# main.net
KiCad netlist of a schematic drawn in Altium Designer
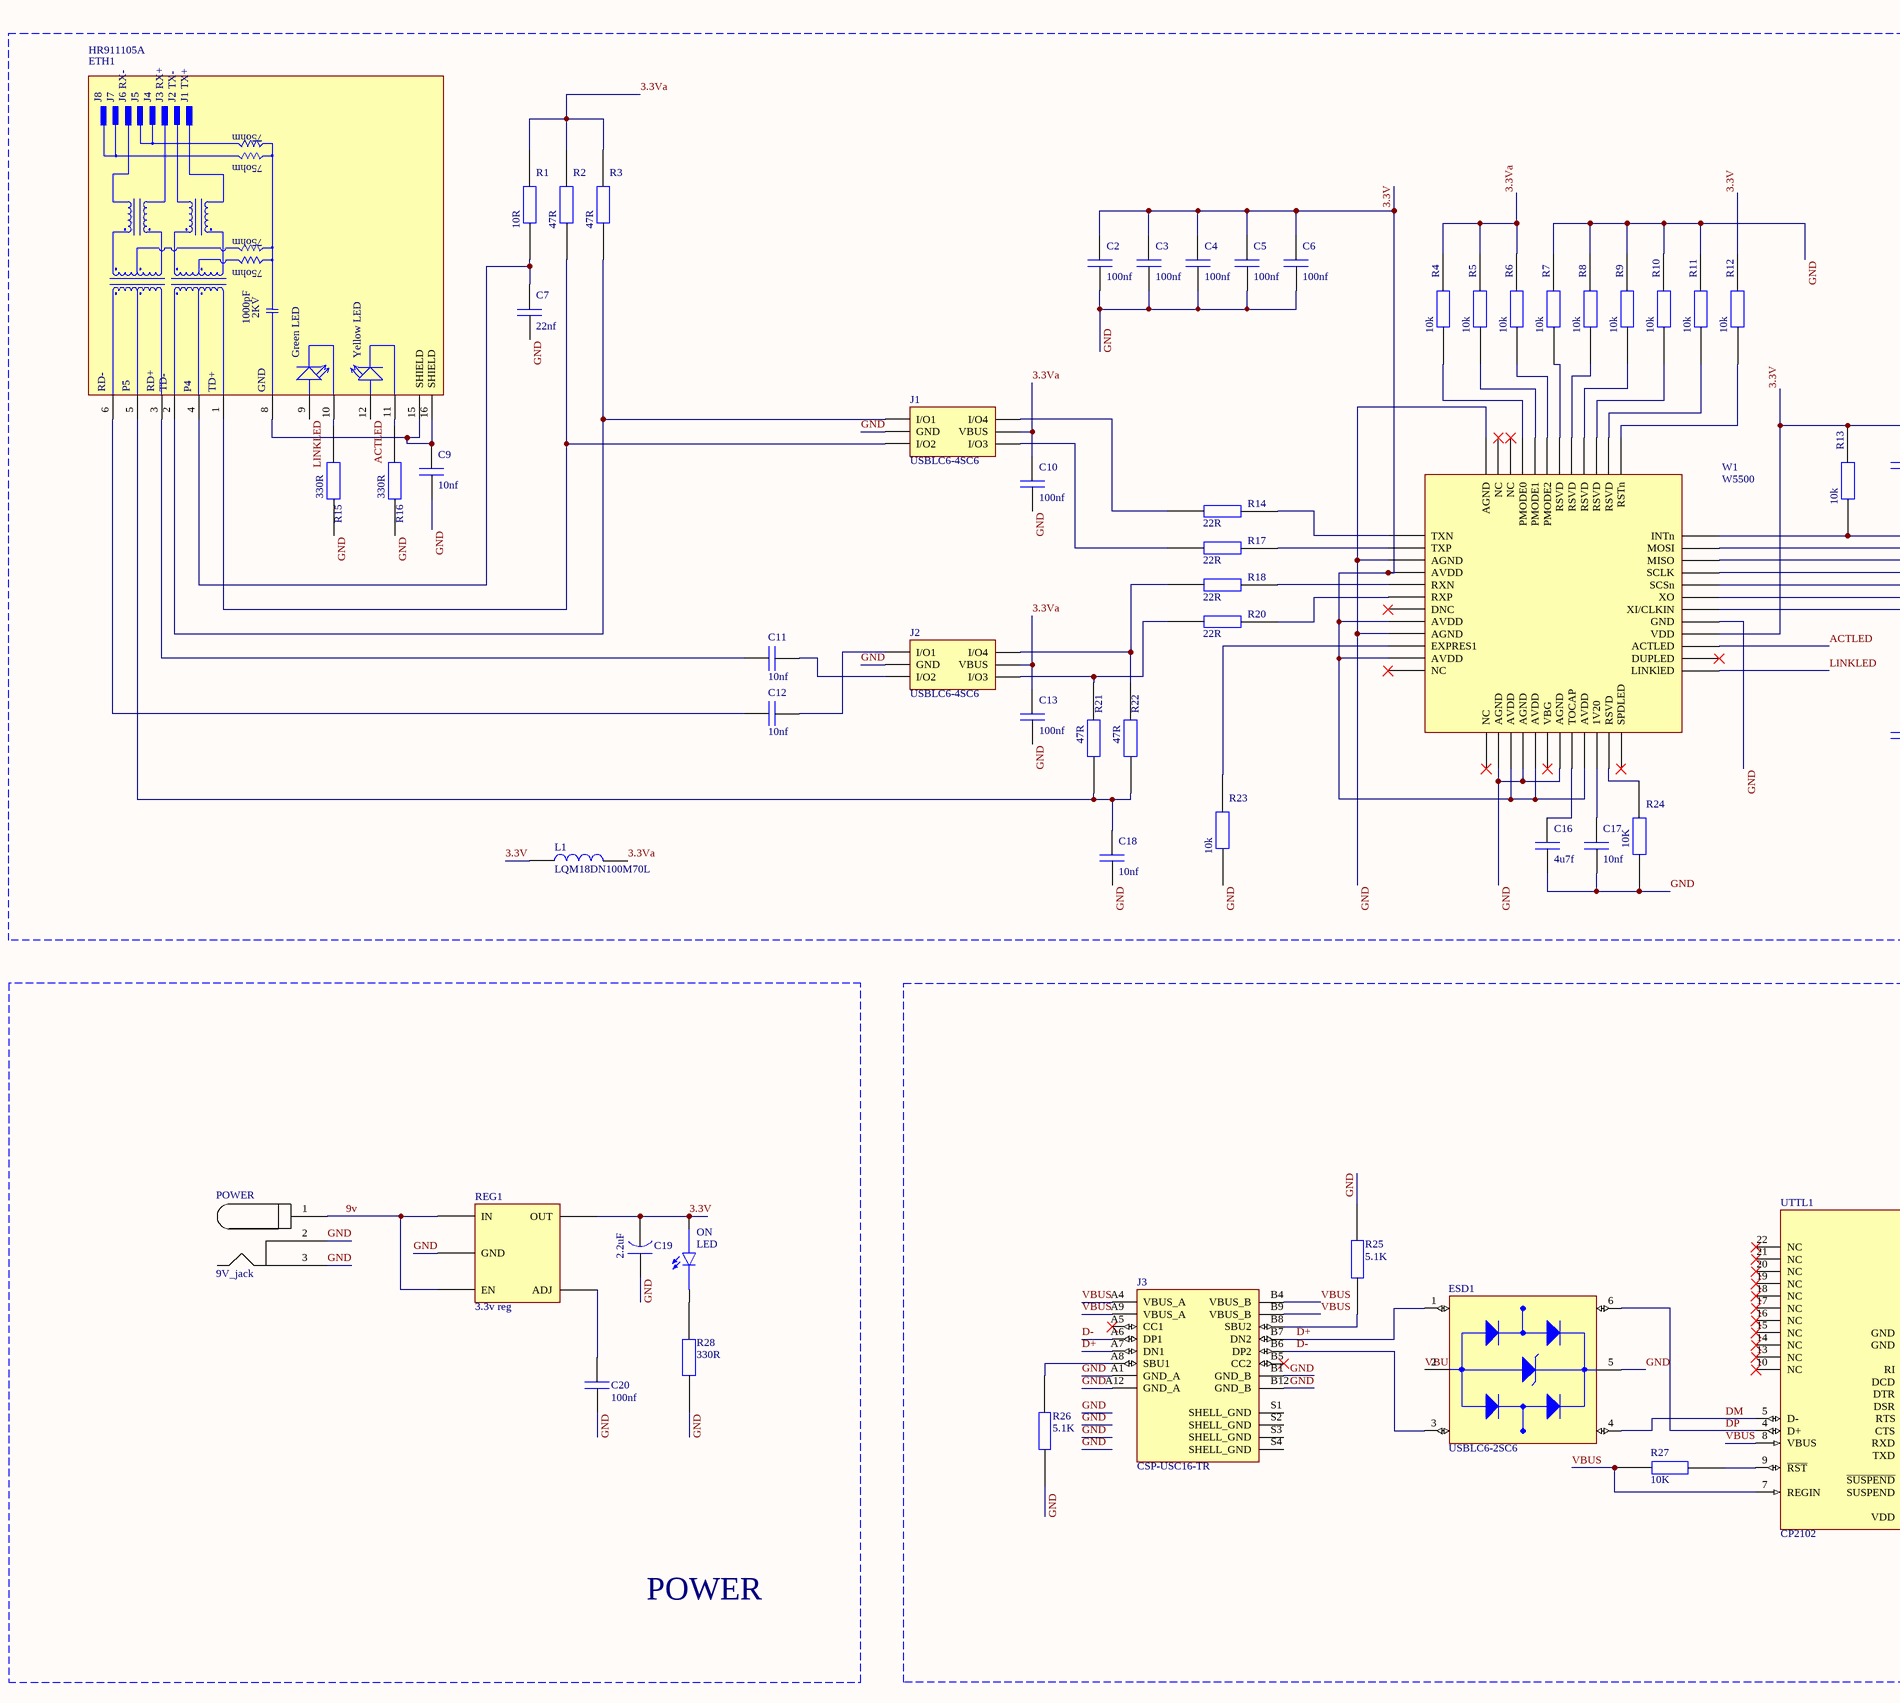
[diagram p0: main.SchDoc, left]
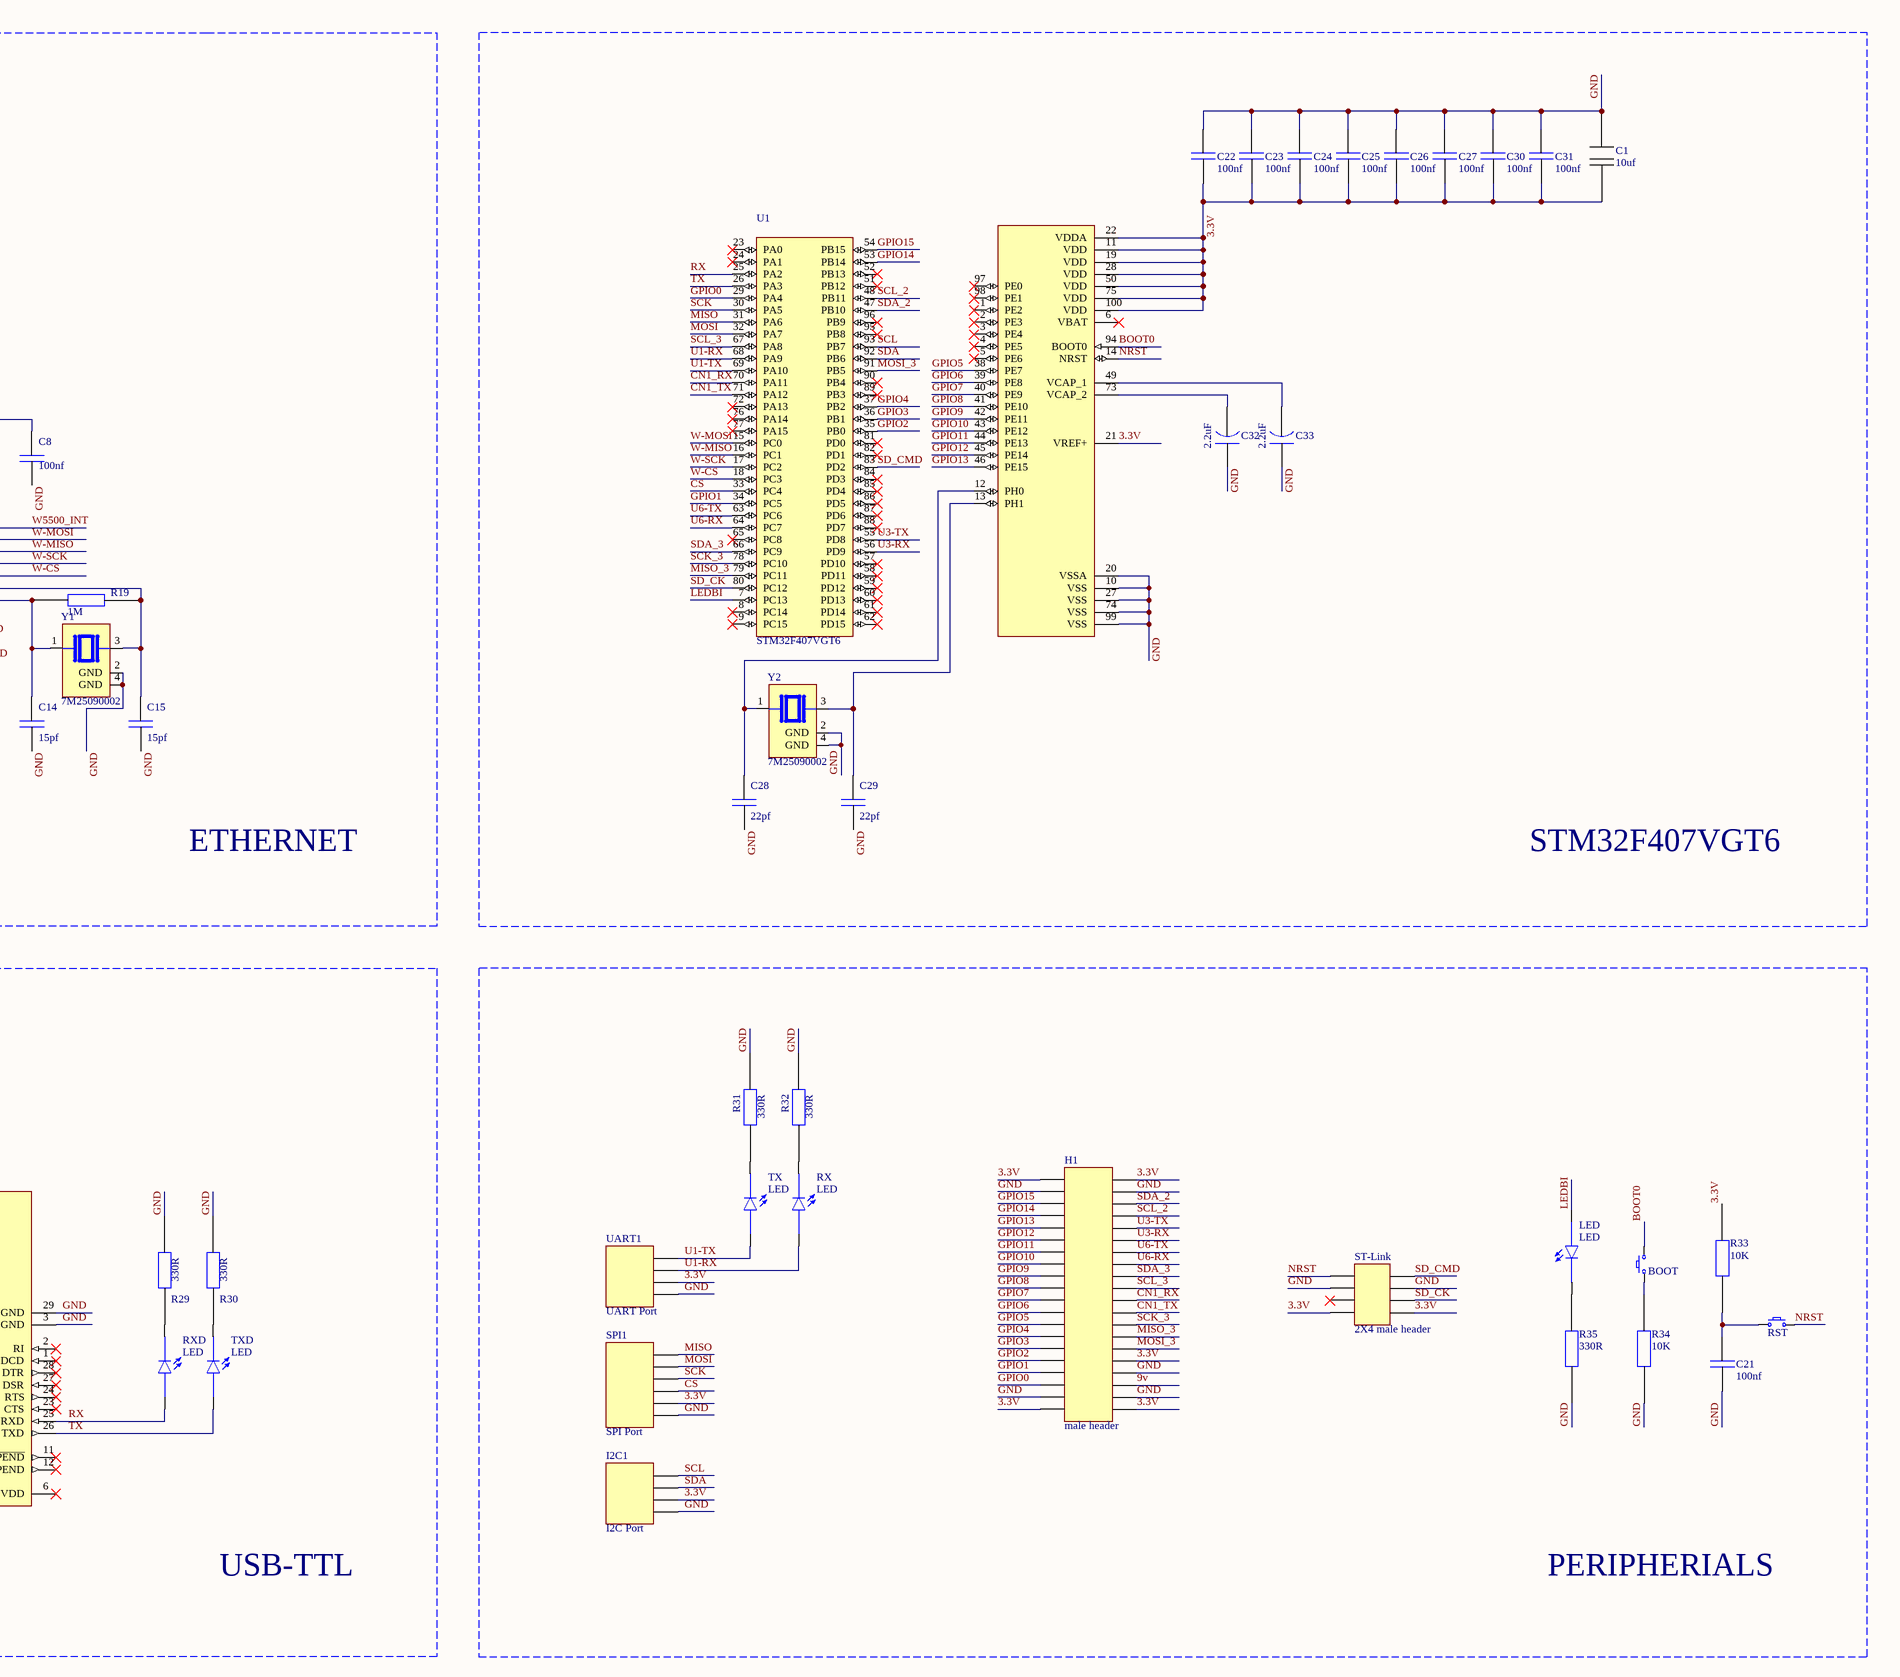
[diagram p1: main.SchDoc, right]

(export (version "E")
  (design (tool "Eeschema 10.0.6"))
  (components
    (comp (ref "BOOT")
      (value "Button_SMD_1")
      (footprint "Button_SMD_1")
      (libsource (lib "Integrated_Library1") (part "Button_SMD_1"))
    )
    (comp (ref "C1")
      (value "10uf")
      (footprint "TANTAL_CAP")
      (libsource (lib "Integrated_Library1") (part "tan_cap"))
    )
    (comp (ref "C2")
      (value "100nf")
      (footprint "0603 CAP")
      (libsource (lib "Integrated_Library1") (part "0603 CAP"))
    )
    (comp (ref "C3")
      (value "100nf")
      (footprint "0603 CAP")
      (libsource (lib "Integrated_Library1") (part "0603 CAP"))
    )
    (comp (ref "C4")
      (value "100nf")
      (footprint "0603 CAP")
      (libsource (lib "Integrated_Library1") (part "0603 CAP"))
    )
    (comp (ref "C5")
      (value "100nf")
      (footprint "0603 CAP")
      (libsource (lib "Integrated_Library1") (part "0603 CAP"))
    )
    (comp (ref "C6")
      (value "100nf")
      (footprint "0603 CAP")
      (libsource (lib "Integrated_Library1") (part "0603 CAP"))
    )
    (comp (ref "C7")
      (value "22nf")
      (footprint "0603 CAP")
      (libsource (lib "Integrated_Library1") (part "0603 CAP"))
    )
    (comp (ref "C8")
      (value "100nf")
      (footprint "0603 CAP")
      (libsource (lib "Integrated_Library1") (part "0603 CAP"))
    )
    (comp (ref "C9")
      (value "10nf")
      (footprint "0603 CAP")
      (libsource (lib "Integrated_Library1") (part "0603 CAP"))
    )
    (comp (ref "C10")
      (value "100nf")
      (footprint "0603 CAP")
      (libsource (lib "Integrated_Library1") (part "0603 CAP"))
    )
    (comp (ref "C11")
      (value "10nf")
      (footprint "0603 CAP")
      (libsource (lib "Integrated_Library1") (part "0603 CAP"))
    )
    (comp (ref "C12")
      (value "10nf")
      (footprint "0603 CAP")
      (libsource (lib "Integrated_Library1") (part "0603 CAP"))
    )
    (comp (ref "C13")
      (value "100nf")
      (footprint "0603 CAP")
      (libsource (lib "Integrated_Library1") (part "0603 CAP"))
    )
    (comp (ref "C14")
      (value "15pf")
      (footprint "0603 CAP")
      (libsource (lib "Integrated_Library1") (part "0603 CAP"))
    )
    (comp (ref "C15")
      (value "15pf")
      (footprint "0603 CAP")
      (libsource (lib "Integrated_Library1") (part "0603 CAP"))
    )
    (comp (ref "C16")
      (value "4u7f")
      (footprint "0603 CAP")
      (libsource (lib "Integrated_Library1") (part "0603 CAP"))
    )
    (comp (ref "C17")
      (value "10nf")
      (footprint "0603 CAP")
      (libsource (lib "Integrated_Library1") (part "0603 CAP"))
    )
    (comp (ref "C18")
      (value "10nf")
      (footprint "0603 CAP")
      (libsource (lib "Integrated_Library1") (part "0603 CAP"))
    )
    (comp (ref "C19")
      (value "2.2uF")
      (footprint "2.2uF TAN CAP")
      (libsource (lib "Integrated_Library1") (part "2.2uF TAN CAP"))
    )
    (comp (ref "C20")
      (value "100nf")
      (footprint "0603 CAP")
      (libsource (lib "Integrated_Library1") (part "0603 CAP"))
    )
    (comp (ref "C21")
      (value "100nf")
      (footprint "0603 CAP")
      (libsource (lib "Integrated_Library1") (part "0603 CAP"))
    )
    (comp (ref "C22")
      (value "100nf")
      (footprint "0603 CAP")
      (libsource (lib "Integrated_Library1") (part "0603 CAP"))
    )
    (comp (ref "C23")
      (value "100nf")
      (footprint "0603 CAP")
      (libsource (lib "Integrated_Library1") (part "0603 CAP"))
    )
    (comp (ref "C24")
      (value "100nf")
      (footprint "0603 CAP")
      (libsource (lib "Integrated_Library1") (part "0603 CAP"))
    )
    (comp (ref "C25")
      (value "100nf")
      (footprint "0603 CAP")
      (libsource (lib "Integrated_Library1") (part "0603 CAP"))
    )
    (comp (ref "C26")
      (value "100nf")
      (footprint "0603 CAP")
      (libsource (lib "Integrated_Library1") (part "0603 CAP"))
    )
    (comp (ref "C27")
      (value "100nf")
      (footprint "0603 CAP")
      (libsource (lib "Integrated_Library1") (part "0603 CAP"))
    )
    (comp (ref "C28")
      (value "22pf")
      (footprint "0603 CAP")
      (libsource (lib "Integrated_Library1") (part "0603 CAP"))
    )
    (comp (ref "C29")
      (value "22pf")
      (footprint "0603 CAP")
      (libsource (lib "Integrated_Library1") (part "0603 CAP"))
    )
    (comp (ref "C30")
      (value "100nf")
      (footprint "0603 CAP")
      (libsource (lib "Integrated_Library1") (part "0603 CAP"))
    )
    (comp (ref "C31")
      (value "100nf")
      (footprint "0603 CAP")
      (libsource (lib "Integrated_Library1") (part "0603 CAP"))
    )
    (comp (ref "C32")
      (value "2.2uF")
      (footprint "2.2uF TAN CAP")
      (libsource (lib "Integrated_Library1") (part "2.2uF TAN CAP"))
    )
    (comp (ref "C33")
      (value "2.2uF")
      (footprint "2.2uF TAN CAP")
      (libsource (lib "Integrated_Library1") (part "2.2uF TAN CAP"))
    )
    (comp (ref "ESD1")
      (value "USBLC6-2SC6")
      (footprint "SOT95P280X145-6N")
      (description "17V Clamp 5A (8/20Âµs) Ipp Tvs Diode Surface Mount SOT-23-6")
      (fields (field (name "MF") "STMicroelectronics"))
      (libsource (lib "Integrated_Library1") (part "USBLC6-2SC6"))
    )
    (comp (ref "ETH1")
      (value "HR911105A")
      (footprint "HANRUN_HR911105A")
      (description "DIP RJ45 Connector;")
      (fields (field (name "MF") "hanrun"))
      (libsource (lib "Integrated_Library1") (part "HR911105A"))
    )
    (comp (ref "H1")
      (value "male header")
      (footprint "2x20 Male Header")
      (description "2x20 male header")
      (libsource (lib "Integrated_Library1") (part "2x20 male header"))
    )
    (comp (ref "I2C1")
      (value "I2C Port")
      (footprint "JST_4P_SMD_FLAT")
      (libsource (lib "Integrated_Library1") (part "JST_4P_SMD_FLAT"))
    )
    (comp (ref "J1")
      (value "USBLC6-4SC6")
      (footprint "SOT23-6L")
      (description "17V Clamp 5A (8/20µs) Ipp Tvs Diode Surface Mount SOT-23-6")
      (fields (field (name "MF") "STMicroelectronics"))
      (libsource (lib "Integrated_Library1") (part "USBLC6-4SC6"))
    )
    (comp (ref "J2")
      (value "USBLC6-4SC6")
      (footprint "SOT23-6L")
      (description "17V Clamp 5A (8/20µs) Ipp Tvs Diode Surface Mount SOT-23-6")
      (fields (field (name "MF") "STMicroelectronics"))
      (libsource (lib "Integrated_Library1") (part "USBLC6-4SC6"))
    )
    (comp (ref "J3")
      (value "CSP-USC16-TR")
      (footprint "VALCON_CSP-USC16-TR")
      (description "CSP-USC16-TR Valcon USB Type C Surface Mount PCB Socket")
      (fields (field (name "MF") "Valcon"))
      (libsource (lib "Integrated_Library1") (part "CSP-USC16-TR"))
    )
    (comp (ref "L1")
      (value "LQM18DN100M70L")
      (footprint "INDC1608X95N")
      (description "Inductor with Inductance 10uH Tol.+/-20% Package 0603 (1608)")
      (fields (field (name "MF") "Murata Electronics"))
      (libsource (lib "LQM18DN100M70L") (part "LQM18DN100M70L"))
    )
    (comp (ref "LED")
      (value "LED")
      (footprint "LEDSC160X80X70L45N")
      (description "Red 626nm LED Indication - Discrete 1.9V 0603 _1608 Metric_")
      (fields (field (name "MP") "597-5004-407F") (field (name "MF") "Dialight"))
      (libsource (lib "597-5004-407F") (part "LED"))
    )
    (comp (ref "ON")
      (value "LED")
      (footprint "LEDSC160X80X70L45N")
      (description "Red 626nm LED Indication - Discrete 1.9V 0603 _1608 Metric_")
      (fields (field (name "MP") "597-5004-407F") (field (name "MF") "Dialight"))
      (libsource (lib "597-5004-407F") (part "LED"))
    )
    (comp (ref "POWER")
      (value "9V_jack")
      (footprint "9V_JACK")
      (libsource (lib "Integrated_Library1") (part "9V_JACK"))
    )
    (comp (ref "R1")
      (value "10R")
      (footprint "0603 RES")
      (libsource (lib "Integrated_Library1") (part "0603 RES"))
    )
    (comp (ref "R2")
      (value "47R")
      (footprint "0603 RES")
      (libsource (lib "Integrated_Library1") (part "0603 RES"))
    )
    (comp (ref "R3")
      (value "47R")
      (footprint "0603 RES")
      (libsource (lib "Integrated_Library1") (part "0603 RES"))
    )
    (comp (ref "R4")
      (value "10k")
      (footprint "0603 RES")
      (libsource (lib "Integrated_Library1") (part "0603 RES"))
    )
    (comp (ref "R5")
      (value "10k")
      (footprint "0603 RES")
      (libsource (lib "Integrated_Library1") (part "0603 RES"))
    )
    (comp (ref "R6")
      (value "10k")
      (footprint "0603 RES")
      (libsource (lib "Integrated_Library1") (part "0603 RES"))
    )
    (comp (ref "R7")
      (value "10k")
      (footprint "0603 RES")
      (libsource (lib "Integrated_Library1") (part "0603 RES"))
    )
    (comp (ref "R8")
      (value "10k")
      (footprint "0603 RES")
      (libsource (lib "Integrated_Library1") (part "0603 RES"))
    )
    (comp (ref "R9")
      (value "10k")
      (footprint "0603 RES")
      (libsource (lib "Integrated_Library1") (part "0603 RES"))
    )
    (comp (ref "R10")
      (value "10k")
      (footprint "0603 RES")
      (libsource (lib "Integrated_Library1") (part "0603 RES"))
    )
    (comp (ref "R11")
      (value "10k")
      (footprint "0603 RES")
      (libsource (lib "Integrated_Library1") (part "0603 RES"))
    )
    (comp (ref "R12")
      (value "10k")
      (footprint "0603 RES")
      (libsource (lib "Integrated_Library1") (part "0603 RES"))
    )
    (comp (ref "R13")
      (value "10k")
      (footprint "0603 RES")
      (libsource (lib "Integrated_Library1") (part "0603 RES"))
    )
    (comp (ref "R14")
      (value "22R")
      (footprint "0603 RES")
      (libsource (lib "Integrated_Library1") (part "0603 RES"))
    )
    (comp (ref "R15")
      (value "330R")
      (footprint "0603 RES")
      (libsource (lib "Integrated_Library1") (part "0603 RES"))
    )
    (comp (ref "R16")
      (value "330R")
      (footprint "0603 RES")
      (libsource (lib "Integrated_Library1") (part "0603 RES"))
    )
    (comp (ref "R17")
      (value "22R")
      (footprint "0603 RES")
      (libsource (lib "Integrated_Library1") (part "0603 RES"))
    )
    (comp (ref "R18")
      (value "22R")
      (footprint "0603 RES")
      (libsource (lib "Integrated_Library1") (part "0603 RES"))
    )
    (comp (ref "R19")
      (value "1M")
      (footprint "0603 RES")
      (libsource (lib "Integrated_Library1") (part "0603 RES"))
    )
    (comp (ref "R20")
      (value "22R")
      (footprint "0603 RES")
      (libsource (lib "Integrated_Library1") (part "0603 RES"))
    )
    (comp (ref "R21")
      (value "47R")
      (footprint "0603 RES")
      (libsource (lib "Integrated_Library1") (part "0603 RES"))
    )
    (comp (ref "R22")
      (value "47R")
      (footprint "0603 RES")
      (libsource (lib "Integrated_Library1") (part "0603 RES"))
    )
    (comp (ref "R23")
      (value "10k")
      (footprint "0603 RES")
      (libsource (lib "Integrated_Library1") (part "0603 RES"))
    )
    (comp (ref "R24")
      (value "10K")
      (footprint "0603 RES")
      (libsource (lib "Integrated_Library1") (part "0603 RES"))
    )
    (comp (ref "R25")
      (value "5.1K")
      (footprint "0603 RES")
      (libsource (lib "Integrated_Library1") (part "0603 RES"))
    )
    (comp (ref "R26")
      (value "5.1K")
      (footprint "0603 RES")
      (libsource (lib "Integrated_Library1") (part "0603 RES"))
    )
    (comp (ref "R27")
      (value "10K")
      (footprint "0603 RES")
      (libsource (lib "Integrated_Library1") (part "0603 RES"))
    )
    (comp (ref "R28")
      (value "330R")
      (footprint "0603 RES")
      (libsource (lib "Integrated_Library1") (part "0603 RES"))
    )
    (comp (ref "R29")
      (value "330R")
      (footprint "0603 RES")
      (libsource (lib "Integrated_Library1") (part "0603 RES"))
    )
    (comp (ref "R30")
      (value "330R")
      (footprint "0603 RES")
      (libsource (lib "Integrated_Library1") (part "0603 RES"))
    )
    (comp (ref "R31")
      (value "330R")
      (footprint "0603 RES")
      (libsource (lib "Integrated_Library1") (part "0603 RES"))
    )
    (comp (ref "R32")
      (value "330R")
      (footprint "0603 RES")
      (libsource (lib "Integrated_Library1") (part "0603 RES"))
    )
    (comp (ref "R33")
      (value "10K")
      (footprint "0603 RES")
      (libsource (lib "Integrated_Library1") (part "0603 RES"))
    )
    (comp (ref "R34")
      (value "10K")
      (footprint "0603 RES")
      (libsource (lib "Integrated_Library1") (part "0603 RES"))
    )
    (comp (ref "R35")
      (value "330R")
      (footprint "0603 RES")
      (libsource (lib "Integrated_Library1") (part "0603 RES"))
    )
    (comp (ref "REG1")
      (value "3.3v reg")
      (footprint "3.3v reg")
      (libsource (lib "Integrated_Library1") (part "3.3v reg"))
    )
    (comp (ref "RST")
      (value "Button_SMD_1")
      (footprint "Button_SMD_1")
      (libsource (lib "Integrated_Library1") (part "Button_SMD_1"))
    )
    (comp (ref "RX")
      (value "LED")
      (footprint "LEDSC160X80X70L45N")
      (description "Red 626nm LED Indication - Discrete 1.9V 0603 _1608 Metric_")
      (fields (field (name "MP") "597-5004-407F") (field (name "MF") "Dialight"))
      (libsource (lib "597-5004-407F") (part "LED"))
    )
    (comp (ref "RXD")
      (value "LED")
      (footprint "LEDSC160X80X70L45N")
      (description "Red 626nm LED Indication - Discrete 1.9V 0603 _1608 Metric_")
      (fields (field (name "MP") "597-5004-407F") (field (name "MF") "Dialight"))
      (libsource (lib "597-5004-407F") (part "LED"))
    )
    (comp (ref "SPI1")
      (value "SPI Port")
      (footprint "JST_6P_SMD_FLAT")
      (libsource (lib "Integrated_Library1") (part "JST_6P_SMD_FLAT"))
    )
    (comp (ref "ST-Link")
      (value "2X4 male header")
      (footprint "2X4 male header - duplicate")
      (description "2.54 pitch 2X4 male header")
      (libsource (lib "Integrated_Library1") (part "2X4 male header"))
    )
    (comp (ref "TX")
      (value "LED")
      (footprint "LEDSC160X80X70L45N")
      (description "Red 626nm LED Indication - Discrete 1.9V 0603 _1608 Metric_")
      (fields (field (name "MP") "597-5004-407F") (field (name "MF") "Dialight"))
      (libsource (lib "597-5004-407F") (part "LED"))
    )
    (comp (ref "TXD")
      (value "LED")
      (footprint "LEDSC160X80X70L45N")
      (description "Red 626nm LED Indication - Discrete 1.9V 0603 _1608 Metric_")
      (fields (field (name "MP") "597-5004-407F") (field (name "MF") "Dialight"))
      (libsource (lib "597-5004-407F") (part "LED"))
    )
    (comp (ref "U1")
      (value "STM32F407VGT6")
      (footprint "QFP50P1600X1600X160-100N")
      (description "STM32 Series 32-bit 1 MB Flash 192 kB RAM ARM Based Microcontroller - LQFP-100")
      (libsource (lib "Integrated_Library1") (part "STM32F407VGT6"))
    )
    (comp (ref "UART1")
      (value "UART Port")
      (footprint "JST_4P_SMD_FLAT")
      (libsource (lib "Integrated_Library1") (part "JST_4P_SMD_FLAT"))
    )
    (comp (ref "UTTL1")
      (value "CP2102")
      (footprint "QFN50P500X500X100-29N")
      (description "CP2102N USB 2.0 to UART (RS232) Bridge Interface Evaluation Board")
      (fields (field (name "MF") "Silicon Labs"))
      (libsource (lib "Integrated_Library1") (part "CP2102"))
    )
    (comp (ref "W1")
      (value "W5500")
      (footprint "W5500")
      (libsource (lib "Integrated_Library1") (part "W5500"))
    )
    (comp (ref "Y1")
      (value "7M25090002")
      (footprint "XTAL_7M25090002")
      (description "25 MHz Â±10ppm Crystal 18pF 4-SMD, No Lead")
      (fields (field (name "MF") "TXC"))
      (libsource (lib "Integrated_Library1") (part "7M25090002"))
    )
    (comp (ref "Y2")
      (value "7M25090002")
      (footprint "XTAL_7M25090002")
      (description "25 MHz Â±10ppm Crystal 18pF 4-SMD, No Lead")
      (fields (field (name "MF") "TXC"))
      (libsource (lib "Integrated_Library1") (part "7M25090002"))
    )
  )
  (nets
    (net (code "1") (name "/3.3V") (class "Default")
      (node (ref "C1") (pin "2") (pinfunction "33_2") (pintype "passive"))
      (node (ref "C19") (pin "2") (pinfunction "82_2") (pintype "passive"))
      (node (ref "C2") (pin "2") (pinfunction "74_2") (pintype "passive"))
      (node (ref "C22") (pin "2") (pinfunction "74_2") (pintype "passive"))
      (node (ref "C23") (pin "2") (pinfunction "74_2") (pintype "passive"))
      (node (ref "C24") (pin "2") (pinfunction "74_2") (pintype "passive"))
      (node (ref "C25") (pin "2") (pinfunction "74_2") (pintype "passive"))
      (node (ref "C26") (pin "2") (pinfunction "74_2") (pintype "passive"))
      (node (ref "C27") (pin "2") (pinfunction "74_2") (pintype "passive"))
      (node (ref "C3") (pin "2") (pinfunction "74_2") (pintype "passive"))
      (node (ref "C30") (pin "2") (pinfunction "74_2") (pintype "passive"))
      (node (ref "C31") (pin "2") (pinfunction "74_2") (pintype "passive"))
      (node (ref "C4") (pin "2") (pinfunction "74_2") (pintype "passive"))
      (node (ref "C5") (pin "2") (pinfunction "74_2") (pintype "passive"))
      (node (ref "C6") (pin "2") (pinfunction "74_2") (pintype "passive"))
      (node (ref "C8") (pin "2") (pinfunction "74_2") (pintype "passive"))
      (node (ref "H1") (pin "1") (pintype "passive"))
      (node (ref "H1") (pin "20") (pintype "passive"))
      (node (ref "H1") (pin "21") (pintype "passive"))
      (node (ref "H1") (pin "25") (pintype "passive"))
      (node (ref "H1") (pin "40") (pintype "passive"))
      (node (ref "I2C1") (pin "2") (pinfunction "85_2") (pintype "passive"))
      (node (ref "L1") (pin "1") (pinfunction "1_1") (pintype "passive"))
      (node (ref "ON") (pin "A") (pinfunction "A_A") (pintype "passive"))
      (node (ref "R12") (pin "2") (pinfunction "74_2") (pintype "passive"))
      (node (ref "R13") (pin "2") (pinfunction "74_2") (pintype "passive"))
      (node (ref "R33") (pin "2") (pinfunction "74_2") (pintype "passive"))
      (node (ref "REG1") (pin "5") (pinfunction "OUT_5") (pintype "passive"))
      (node (ref "SPI1") (pin "2") (pinfunction "85_2") (pintype "passive"))
      (node (ref "ST-Link") (pin "4") (pintype "passive"))
      (node (ref "ST-Link") (pin "5") (pintype "passive"))
      (node (ref "U1") (pin "100") (pinfunction "VDD_100") (pintype "power_in"))
      (node (ref "U1") (pin "11") (pinfunction "VDD_11") (pintype "power_in"))
      (node (ref "U1") (pin "19") (pinfunction "VDD_19") (pintype "power_in"))
      (node (ref "U1") (pin "21") (pinfunction "VREF+_21") (pintype "power_in"))
      (node (ref "U1") (pin "22") (pinfunction "VDDA_22") (pintype "power_in"))
      (node (ref "U1") (pin "28") (pinfunction "VDD_28") (pintype "power_in"))
      (node (ref "U1") (pin "50") (pinfunction "VDD_50") (pintype "power_in"))
      (node (ref "U1") (pin "75") (pinfunction "VDD_75") (pintype "power_in"))
      (node (ref "UART1") (pin "2") (pinfunction "85_2") (pintype "passive"))
      (node (ref "W1") (pin "11") (pinfunction "AVDD_11") (pintype "passive"))
      (node (ref "W1") (pin "15") (pinfunction "AVDD_15") (pintype "passive"))
      (node (ref "W1") (pin "17") (pinfunction "AVDD_17") (pintype "passive"))
      (node (ref "W1") (pin "21") (pinfunction "AVDD_21") (pintype "passive"))
      (node (ref "W1") (pin "28") (pinfunction "VDD_28") (pintype "passive"))
      (node (ref "W1") (pin "4") (pinfunction "AVDD_4") (pintype "passive"))
      (node (ref "W1") (pin "8") (pinfunction "AVDD_8") (pintype "passive"))
    )
    (net (code "2") (name "/3.3Va") (class "Default")
      (node (ref "C10") (pin "2") (pinfunction "74_2") (pintype "passive"))
      (node (ref "C13") (pin "2") (pinfunction "74_2") (pintype "passive"))
      (node (ref "J1") (pin "5") (pinfunction "VBUS_5") (pintype "passive"))
      (node (ref "J2") (pin "5") (pinfunction "VBUS_5") (pintype "passive"))
      (node (ref "L1") (pin "2") (pinfunction "2_2") (pintype "passive"))
      (node (ref "R1") (pin "2") (pinfunction "74_2") (pintype "passive"))
      (node (ref "R2") (pin "2") (pinfunction "74_2") (pintype "passive"))
      (node (ref "R3") (pin "2") (pinfunction "74_2") (pintype "passive"))
      (node (ref "R4") (pin "2") (pinfunction "74_2") (pintype "passive"))
      (node (ref "R5") (pin "2") (pinfunction "74_2") (pintype "passive"))
      (node (ref "R6") (pin "2") (pinfunction "74_2") (pintype "passive"))
    )
    (net (code "3") (name "/9v") (class "Default")
      (node (ref "H1") (pin "23") (pintype "passive"))
      (node (ref "POWER") (pin "1") (pintype "passive"))
      (node (ref "REG1") (pin "1") (pinfunction "IN_1") (pintype "passive"))
      (node (ref "REG1") (pin "3") (pinfunction "EN_3") (pintype "passive"))
    )
    (net (code "4") (name "/ACTLED") (class "Default")
      (node (ref "ETH1") (pin "12") (pinfunction "YA_12") (pintype "passive"))
      (node (ref "W1") (pin "27") (pinfunction "ACTLED_27") (pintype "passive"))
    )
    (net (code "5") (name "/BOOT0") (class "Default")
      (node (ref "BOOT") (pin "2") (pinfunction "2_2") (pintype "passive"))
      (node (ref "U1") (pin "94") (pinfunction "BOOT0_94") (pintype "input"))
    )
    (net (code "6") (name "/CN1_RX") (class "Default")
      (node (ref "H1") (pin "30") (pintype "passive"))
      (node (ref "U1") (pin "70") (pinfunction "PA11_70") (pintype "bidirectional"))
    )
    (net (code "7") (name "/CN1_TX") (class "Default")
      (node (ref "H1") (pin "29") (pintype "passive"))
      (node (ref "U1") (pin "71") (pinfunction "PA12_71") (pintype "bidirectional"))
    )
    (net (code "8") (name "/CS") (class "Default")
      (node (ref "SPI1") (pin "3") (pinfunction "85_3") (pintype "passive"))
      (node (ref "U1") (pin "33") (pinfunction "PC4_33") (pintype "bidirectional"))
    )
    (net (code "9") (name "/D+") (class "Default")
      (node (ref "ESD1") (pin "1") (pinfunction "I/O1_IN_1") (pintype "bidirectional"))
      (node (ref "J3") (pin "A7") (pinfunction "DN1_A7") (pintype "bidirectional"))
      (node (ref "J3") (pin "B7") (pinfunction "DN2_B7") (pintype "bidirectional"))
    )
    (net (code "10") (name "/D-") (class "Default")
      (node (ref "ESD1") (pin "3") (pinfunction "I/O2_IN_3") (pintype "bidirectional"))
      (node (ref "J3") (pin "A6") (pinfunction "DP1_A6") (pintype "bidirectional"))
      (node (ref "J3") (pin "B6") (pinfunction "DP2_B6") (pintype "bidirectional"))
    )
    (net (code "11") (name "/DM") (class "Default")
      (node (ref "ESD1") (pin "4") (pinfunction "I/O2_OUT_4") (pintype "bidirectional"))
      (node (ref "UTTL1") (pin "5") (pinfunction "D-_5") (pintype "bidirectional"))
    )
    (net (code "12") (name "/DP") (class "Default")
      (node (ref "ESD1") (pin "6") (pinfunction "I/O1_OUT_6") (pintype "bidirectional"))
      (node (ref "UTTL1") (pin "4") (pinfunction "D+_4") (pintype "bidirectional"))
    )
    (net (code "13") (name "/GND") (class "Default")
      (node (ref "C1") (pin "1") (pinfunction "32_1") (pintype "passive"))
      (node (ref "C10") (pin "1") (pinfunction "73_1") (pintype "passive"))
      (node (ref "C13") (pin "1") (pinfunction "73_1") (pintype "passive"))
      (node (ref "C14") (pin "1") (pinfunction "73_1") (pintype "passive"))
      (node (ref "C15") (pin "1") (pinfunction "73_1") (pintype "passive"))
      (node (ref "C16") (pin "1") (pinfunction "73_1") (pintype "passive"))
      (node (ref "C17") (pin "1") (pinfunction "73_1") (pintype "passive"))
      (node (ref "C18") (pin "1") (pinfunction "73_1") (pintype "passive"))
      (node (ref "C19") (pin "1") (pinfunction "83_1") (pintype "passive"))
      (node (ref "C2") (pin "1") (pinfunction "73_1") (pintype "passive"))
      (node (ref "C20") (pin "1") (pinfunction "73_1") (pintype "passive"))
      (node (ref "C21") (pin "1") (pinfunction "73_1") (pintype "passive"))
      (node (ref "C22") (pin "1") (pinfunction "73_1") (pintype "passive"))
      (node (ref "C23") (pin "1") (pinfunction "73_1") (pintype "passive"))
      (node (ref "C24") (pin "1") (pinfunction "73_1") (pintype "passive"))
      (node (ref "C25") (pin "1") (pinfunction "73_1") (pintype "passive"))
      (node (ref "C26") (pin "1") (pinfunction "73_1") (pintype "passive"))
      (node (ref "C27") (pin "1") (pinfunction "73_1") (pintype "passive"))
      (node (ref "C28") (pin "1") (pinfunction "73_1") (pintype "passive"))
      (node (ref "C29") (pin "1") (pinfunction "73_1") (pintype "passive"))
      (node (ref "C3") (pin "1") (pinfunction "73_1") (pintype "passive"))
      (node (ref "C30") (pin "1") (pinfunction "73_1") (pintype "passive"))
      (node (ref "C31") (pin "1") (pinfunction "73_1") (pintype "passive"))
      (node (ref "C32") (pin "1") (pinfunction "83_1") (pintype "passive"))
      (node (ref "C33") (pin "1") (pinfunction "83_1") (pintype "passive"))
      (node (ref "C4") (pin "1") (pinfunction "73_1") (pintype "passive"))
      (node (ref "C5") (pin "1") (pinfunction "73_1") (pintype "passive"))
      (node (ref "C6") (pin "1") (pinfunction "73_1") (pintype "passive"))
      (node (ref "C7") (pin "1") (pinfunction "73_1") (pintype "passive"))
      (node (ref "C8") (pin "1") (pinfunction "73_1") (pintype "passive"))
      (node (ref "C9") (pin "1") (pinfunction "73_1") (pintype "passive"))
      (node (ref "ESD1") (pin "5") (pinfunction "VBUS_5") (pintype "power_in"))
      (node (ref "H1") (pin "19") (pintype "passive"))
      (node (ref "H1") (pin "2") (pintype "passive"))
      (node (ref "H1") (pin "22") (pintype "passive"))
      (node (ref "H1") (pin "24") (pintype "passive"))
      (node (ref "H1") (pin "39") (pintype "passive"))
      (node (ref "I2C1") (pin "1") (pinfunction "84_1") (pintype "passive"))
      (node (ref "J1") (pin "2") (pinfunction "GND_2") (pintype "passive"))
      (node (ref "J2") (pin "2") (pinfunction "GND_2") (pintype "passive"))
      (node (ref "J3") (pin "A1") (pinfunction "GND_A_A1") (pintype "power_in"))
      (node (ref "J3") (pin "A12") (pinfunction "GND_A_A12") (pintype "power_in"))
      (node (ref "J3") (pin "B1") (pinfunction "GND_B_B1") (pintype "power_in"))
      (node (ref "J3") (pin "B12") (pinfunction "GND_B_B12") (pintype "power_in"))
      (node (ref "POWER") (pin "2") (pintype "passive"))
      (node (ref "POWER") (pin "3") (pintype "passive"))
      (node (ref "R10") (pin "2") (pinfunction "74_2") (pintype "passive"))
      (node (ref "R11") (pin "2") (pinfunction "74_2") (pintype "passive"))
      (node (ref "R15") (pin "1") (pinfunction "73_1") (pintype "passive"))
      (node (ref "R16") (pin "1") (pinfunction "73_1") (pintype "passive"))
      (node (ref "R23") (pin "1") (pinfunction "73_1") (pintype "passive"))
      (node (ref "R24") (pin "1") (pinfunction "73_1") (pintype "passive"))
      (node (ref "R25") (pin "2") (pinfunction "74_2") (pintype "passive"))
      (node (ref "R26") (pin "1") (pinfunction "73_1") (pintype "passive"))
      (node (ref "R28") (pin "2") (pinfunction "74_2") (pintype "passive"))
      (node (ref "R29") (pin "2") (pinfunction "74_2") (pintype "passive"))
      (node (ref "R30") (pin "2") (pinfunction "74_2") (pintype "passive"))
      (node (ref "R31") (pin "2") (pinfunction "74_2") (pintype "passive"))
      (node (ref "R32") (pin "2") (pinfunction "74_2") (pintype "passive"))
      (node (ref "R34") (pin "1") (pinfunction "73_1") (pintype "passive"))
      (node (ref "R35") (pin "2") (pinfunction "74_2") (pintype "passive"))
      (node (ref "R7") (pin "2") (pinfunction "74_2") (pintype "passive"))
      (node (ref "R8") (pin "2") (pinfunction "74_2") (pintype "passive"))
      (node (ref "R9") (pin "2") (pinfunction "74_2") (pintype "passive"))
      (node (ref "REG1") (pin "2") (pinfunction "GND_2") (pintype "passive"))
      (node (ref "SPI1") (pin "1") (pinfunction "84_1") (pintype "passive"))
      (node (ref "ST-Link") (pin "2") (pintype "passive"))
      (node (ref "ST-Link") (pin "7") (pintype "passive"))
      (node (ref "U1") (pin "10") (pinfunction "VSS_10") (pintype "power_in"))
      (node (ref "U1") (pin "20") (pinfunction "VSSA_20") (pintype "power_in"))
      (node (ref "U1") (pin "27") (pinfunction "VSS_27") (pintype "power_in"))
      (node (ref "U1") (pin "74") (pinfunction "VSS_74") (pintype "power_in"))
      (node (ref "U1") (pin "99") (pinfunction "VSS_99") (pintype "power_in"))
      (node (ref "UART1") (pin "1") (pinfunction "84_1") (pintype "passive"))
      (node (ref "UTTL1") (pin "29") (pinfunction "GND_29") (pintype "power_in"))
      (node (ref "UTTL1") (pin "3") (pinfunction "GND_3") (pintype "power_in"))
      (node (ref "W1") (pin "14") (pinfunction "AGND_14") (pintype "passive"))
      (node (ref "W1") (pin "16") (pinfunction "AGND_16") (pintype "passive"))
      (node (ref "W1") (pin "19") (pinfunction "AGND_19") (pintype "passive"))
      (node (ref "W1") (pin "29") (pinfunction "GND_29") (pintype "passive"))
      (node (ref "W1") (pin "3") (pinfunction "AGND_3") (pintype "passive"))
      (node (ref "W1") (pin "48") (pinfunction "AGND_48") (pintype "passive"))
      (node (ref "W1") (pin "9") (pinfunction "AGND_9") (pintype "passive"))
      (node (ref "Y1") (pin "2") (pinfunction "GND_2") (pintype "power_in"))
      (node (ref "Y1") (pin "4") (pinfunction "GND_4") (pintype "power_in"))
      (node (ref "Y2") (pin "2") (pinfunction "GND_2") (pintype "power_in"))
      (node (ref "Y2") (pin "4") (pinfunction "GND_4") (pintype "power_in"))
    )
    (net (code "14") (name "/GPIO0") (class "Default")
      (node (ref "H1") (pin "18") (pintype "passive"))
      (node (ref "U1") (pin "29") (pinfunction "PA4_29") (pintype "bidirectional"))
    )
    (net (code "15") (name "/GPIO1") (class "Default")
      (node (ref "H1") (pin "17") (pintype "passive"))
      (node (ref "U1") (pin "34") (pinfunction "PC5_34") (pintype "bidirectional"))
    )
    (net (code "16") (name "/GPIO2") (class "Default")
      (node (ref "H1") (pin "16") (pintype "passive"))
      (node (ref "U1") (pin "35") (pinfunction "PB0_35") (pintype "bidirectional"))
    )
    (net (code "17") (name "/GPIO3") (class "Default")
      (node (ref "H1") (pin "15") (pintype "passive"))
      (node (ref "U1") (pin "36") (pinfunction "PB1_36") (pintype "bidirectional"))
    )
    (net (code "18") (name "/GPIO4") (class "Default")
      (node (ref "H1") (pin "14") (pintype "passive"))
      (node (ref "U1") (pin "37") (pinfunction "PB2_37") (pintype "bidirectional"))
    )
    (net (code "19") (name "/GPIO5") (class "Default")
      (node (ref "H1") (pin "13") (pintype "passive"))
      (node (ref "U1") (pin "38") (pinfunction "PE7_38") (pintype "bidirectional"))
    )
    (net (code "20") (name "/GPIO6") (class "Default")
      (node (ref "H1") (pin "12") (pintype "passive"))
      (node (ref "U1") (pin "39") (pinfunction "PE8_39") (pintype "bidirectional"))
    )
    (net (code "21") (name "/GPIO7") (class "Default")
      (node (ref "H1") (pin "11") (pintype "passive"))
      (node (ref "U1") (pin "40") (pinfunction "PE9_40") (pintype "bidirectional"))
    )
    (net (code "22") (name "/GPIO8") (class "Default")
      (node (ref "H1") (pin "10") (pintype "passive"))
      (node (ref "U1") (pin "41") (pinfunction "PE10_41") (pintype "bidirectional"))
    )
    (net (code "23") (name "/GPIO9") (class "Default")
      (node (ref "H1") (pin "9") (pintype "passive"))
      (node (ref "U1") (pin "42") (pinfunction "PE11_42") (pintype "bidirectional"))
    )
    (net (code "24") (name "/GPIO10") (class "Default")
      (node (ref "H1") (pin "8") (pintype "passive"))
      (node (ref "U1") (pin "43") (pinfunction "PE12_43") (pintype "bidirectional"))
    )
    (net (code "25") (name "/GPIO11") (class "Default")
      (node (ref "H1") (pin "7") (pintype "passive"))
      (node (ref "U1") (pin "44") (pinfunction "PE13_44") (pintype "bidirectional"))
    )
    (net (code "26") (name "/GPIO12") (class "Default")
      (node (ref "H1") (pin "6") (pintype "passive"))
      (node (ref "U1") (pin "45") (pinfunction "PE14_45") (pintype "bidirectional"))
    )
    (net (code "27") (name "/GPIO13") (class "Default")
      (node (ref "H1") (pin "5") (pintype "passive"))
      (node (ref "U1") (pin "46") (pinfunction "PE15_46") (pintype "bidirectional"))
    )
    (net (code "28") (name "/GPIO14") (class "Default")
      (node (ref "H1") (pin "4") (pintype "passive"))
      (node (ref "U1") (pin "53") (pinfunction "PB14_53") (pintype "bidirectional"))
    )
    (net (code "29") (name "/GPIO15") (class "Default")
      (node (ref "H1") (pin "3") (pintype "passive"))
      (node (ref "U1") (pin "54") (pinfunction "PB15_54") (pintype "bidirectional"))
    )
    (net (code "30") (name "/LEDBI") (class "Default")
      (node (ref "LED") (pin "A") (pinfunction "A_A") (pintype "passive"))
      (node (ref "U1") (pin "7") (pinfunction "PC13_7") (pintype "bidirectional"))
    )
    (net (code "31") (name "/LINKLED") (class "Default")
      (node (ref "ETH1") (pin "9") (pinfunction "GA_9") (pintype "passive"))
      (node (ref "W1") (pin "25") (pinfunction "LINKlED_25") (pintype "passive"))
    )
    (net (code "32") (name "/MISO") (class "Default")
      (node (ref "SPI1") (pin "6") (pinfunction "85_6") (pintype "passive"))
      (node (ref "U1") (pin "31") (pinfunction "PA6_31") (pintype "bidirectional"))
    )
    (net (code "33") (name "/MISO_3") (class "Default")
      (node (ref "H1") (pin "27") (pintype "passive"))
      (node (ref "U1") (pin "79") (pinfunction "PC11_79") (pintype "bidirectional"))
    )
    (net (code "34") (name "/MOSI") (class "Default")
      (node (ref "SPI1") (pin "5") (pinfunction "85_5") (pintype "passive"))
      (node (ref "U1") (pin "32") (pinfunction "PA7_32") (pintype "bidirectional"))
    )
    (net (code "35") (name "/MOSI_3") (class "Default")
      (node (ref "H1") (pin "26") (pintype "passive"))
      (node (ref "U1") (pin "91") (pinfunction "PB5_91") (pintype "bidirectional"))
    )
    (net (code "36") (name "/NRST") (class "Default")
      (node (ref "RST") (pin "2") (pinfunction "2_2") (pintype "passive"))
      (node (ref "ST-Link") (pin "1") (pintype "passive"))
      (node (ref "U1") (pin "14") (pinfunction "NRST_14") (pintype "bidirectional"))
    )
    (net (code "37") (name "/RX") (class "Default")
      (node (ref "RXD") (pin "A") (pinfunction "A_A") (pintype "passive"))
      (node (ref "U1") (pin "25") (pinfunction "PA2_25") (pintype "bidirectional"))
      (node (ref "UTTL1") (pin "25") (pinfunction "RXD_25") (pintype "input"))
    )
    (net (code "38") (name "/SCK") (class "Default")
      (node (ref "SPI1") (pin "4") (pinfunction "85_4") (pintype "passive"))
      (node (ref "U1") (pin "30") (pinfunction "PA5_30") (pintype "bidirectional"))
    )
    (net (code "39") (name "/SCK_3") (class "Default")
      (node (ref "H1") (pin "28") (pintype "passive"))
      (node (ref "U1") (pin "78") (pinfunction "PC10_78") (pintype "bidirectional"))
    )
    (net (code "40") (name "/SCL") (class "Default")
      (node (ref "I2C1") (pin "4") (pinfunction "85_4") (pintype "passive"))
      (node (ref "U1") (pin "93") (pinfunction "PB7_93") (pintype "bidirectional"))
    )
    (net (code "41") (name "/SCL_2") (class "Default")
      (node (ref "H1") (pin "37") (pintype "passive"))
      (node (ref "U1") (pin "48") (pinfunction "PB11_48") (pintype "bidirectional"))
    )
    (net (code "42") (name "/SCL_3") (class "Default")
      (node (ref "H1") (pin "31") (pintype "passive"))
      (node (ref "U1") (pin "67") (pinfunction "PA8_67") (pintype "bidirectional"))
    )
    (net (code "43") (name "/SDA") (class "Default")
      (node (ref "I2C1") (pin "3") (pinfunction "85_3") (pintype "passive"))
      (node (ref "U1") (pin "92") (pinfunction "PB6_92") (pintype "bidirectional"))
    )
    (net (code "44") (name "/SDA_2") (class "Default")
      (node (ref "H1") (pin "38") (pintype "passive"))
      (node (ref "U1") (pin "47") (pinfunction "PB10_47") (pintype "bidirectional"))
    )
    (net (code "45") (name "/SDA_3") (class "Default")
      (node (ref "H1") (pin "32") (pintype "passive"))
      (node (ref "U1") (pin "66") (pinfunction "PC9_66") (pintype "bidirectional"))
    )
    (net (code "46") (name "/SD_CK") (class "Default")
      (node (ref "ST-Link") (pin "6") (pintype "passive"))
      (node (ref "U1") (pin "80") (pinfunction "PC12_80") (pintype "bidirectional"))
    )
    (net (code "47") (name "/SD_CMD") (class "Default")
      (node (ref "ST-Link") (pin "8") (pintype "passive"))
      (node (ref "U1") (pin "83") (pinfunction "PD2_83") (pintype "bidirectional"))
    )
    (net (code "48") (name "/TX") (class "Default")
      (node (ref "TXD") (pin "A") (pinfunction "A_A") (pintype "passive"))
      (node (ref "U1") (pin "26") (pinfunction "PA3_26") (pintype "bidirectional"))
      (node (ref "UTTL1") (pin "26") (pinfunction "TXD_26") (pintype "output"))
    )
    (net (code "49") (name "/U1-RX") (class "Default")
      (node (ref "RX") (pin "A") (pinfunction "A_A") (pintype "passive"))
      (node (ref "U1") (pin "68") (pinfunction "PA9_68") (pintype "bidirectional"))
      (node (ref "UART1") (pin "3") (pinfunction "85_3") (pintype "passive"))
    )
    (net (code "50") (name "/U1-TX") (class "Default")
      (node (ref "TX") (pin "A") (pinfunction "A_A") (pintype "passive"))
      (node (ref "U1") (pin "69") (pinfunction "PA10_69") (pintype "bidirectional"))
      (node (ref "UART1") (pin "4") (pinfunction "85_4") (pintype "passive"))
    )
    (net (code "51") (name "/U3-RX") (class "Default")
      (node (ref "H1") (pin "35") (pintype "passive"))
      (node (ref "U1") (pin "56") (pinfunction "PD9_56") (pintype "bidirectional"))
    )
    (net (code "52") (name "/U3-TX") (class "Default")
      (node (ref "H1") (pin "36") (pintype "passive"))
      (node (ref "U1") (pin "55") (pinfunction "PD8_55") (pintype "bidirectional"))
    )
    (net (code "53") (name "/U6-RX") (class "Default")
      (node (ref "H1") (pin "33") (pintype "passive"))
      (node (ref "U1") (pin "64") (pinfunction "PC7_64") (pintype "bidirectional"))
    )
    (net (code "54") (name "/U6-TX") (class "Default")
      (node (ref "H1") (pin "34") (pintype "passive"))
      (node (ref "U1") (pin "63") (pinfunction "PC6_63") (pintype "bidirectional"))
    )
    (net (code "55") (name "/VBUS") (class "Default")
      (node (ref "ESD1") (pin "2") (pinfunction "GND_2") (pintype "power_in"))
      (node (ref "J3") (pin "A4") (pinfunction "VBUS_A_A4") (pintype "power_in"))
      (node (ref "J3") (pin "A9") (pinfunction "VBUS_A_A9") (pintype "power_in"))
      (node (ref "J3") (pin "B4") (pinfunction "VBUS_B_B4") (pintype "power_in"))
      (node (ref "J3") (pin "B9") (pinfunction "VBUS_B_B9") (pintype "power_in"))
      (node (ref "R27") (pin "1") (pinfunction "73_1") (pintype "passive"))
      (node (ref "UTTL1") (pin "7") (pinfunction "REGIN_7") (pintype "input"))
      (node (ref "UTTL1") (pin "8") (pinfunction "VBUS_8") (pintype "input"))
    )
    (net (code "56") (name "/W-CS") (class "Default")
      (node (ref "U1") (pin "18") (pinfunction "PC3_18") (pintype "bidirectional"))
      (node (ref "W1") (pin "32") (pinfunction "SCSn_32") (pintype "passive"))
    )
    (net (code "57") (name "/W-MISO") (class "Default")
      (node (ref "U1") (pin "16") (pinfunction "PC1_16") (pintype "bidirectional"))
      (node (ref "W1") (pin "34") (pinfunction "MISO_34") (pintype "passive"))
    )
    (net (code "58") (name "/W-MOSI") (class "Default")
      (node (ref "U1") (pin "15") (pinfunction "PC0_15") (pintype "bidirectional"))
      (node (ref "W1") (pin "35") (pinfunction "MOSI_35") (pintype "passive"))
    )
    (net (code "59") (name "/W-SCK") (class "Default")
      (node (ref "U1") (pin "17") (pinfunction "PC2_17") (pintype "bidirectional"))
      (node (ref "W1") (pin "33") (pinfunction "SCLK_33") (pintype "passive"))
    )
    (net (code "60") (name "/W5500_INT") (class "Default")
      (node (ref "R13") (pin "1") (pinfunction "73_1") (pintype "passive"))
      (node (ref "W1") (pin "36") (pinfunction "INTn_36") (pintype "passive"))
    )
    (net (code "61") (name "Net-(C7-74)") (class "Default")
      (node (ref "C7") (pin "2") (pinfunction "74_2") (pintype "passive"))
      (node (ref "ETH1") (pin "4") (pinfunction "P4_4") (pintype "passive"))
      (node (ref "R1") (pin "1") (pinfunction "73_1") (pintype "passive"))
    )
    (net (code "62") (name "Net-(C9-74)") (class "Default")
      (node (ref "C9") (pin "2") (pinfunction "74_2") (pintype "passive"))
      (node (ref "ETH1") (pin "15") (pinfunction "SHIELD_15") (pintype "passive"))
      (node (ref "ETH1") (pin "16") (pinfunction "SHIELD_16") (pintype "passive"))
      (node (ref "ETH1") (pin "8") (pinfunction "GND_8") (pintype "power_in"))
    )
    (net (code "63") (name "Net-(C11-73)") (class "Default")
      (node (ref "C11") (pin "1") (pinfunction "73_1") (pintype "passive"))
      (node (ref "ETH1") (pin "3") (pinfunction "RD+_3") (pintype "passive"))
    )
    (net (code "64") (name "Net-(C11-74)") (class "Default")
      (node (ref "C11") (pin "2") (pinfunction "74_2") (pintype "passive"))
      (node (ref "J2") (pin "3") (pinfunction "I/O2_3") (pintype "passive"))
    )
    (net (code "65") (name "Net-(C12-73)") (class "Default")
      (node (ref "C12") (pin "1") (pinfunction "73_1") (pintype "passive"))
      (node (ref "ETH1") (pin "6") (pinfunction "RD-_6") (pintype "passive"))
    )
    (net (code "66") (name "Net-(C12-74)") (class "Default")
      (node (ref "C12") (pin "2") (pinfunction "74_2") (pintype "passive"))
      (node (ref "J2") (pin "1") (pinfunction "I/O1_1") (pintype "passive"))
    )
    (net (code "67") (name "Net-(C14-74)") (class "Default")
      (node (ref "C14") (pin "2") (pinfunction "74_2") (pintype "passive"))
      (node (ref "R19") (pin "1") (pinfunction "73_1") (pintype "passive"))
      (node (ref "W1") (pin "30") (pinfunction "XI/CLKIN_30") (pintype "passive"))
      (node (ref "Y1") (pin "1") (pinfunction "1_1") (pintype "passive"))
    )
    (net (code "68") (name "Net-(C15-74)") (class "Default")
      (node (ref "C15") (pin "2") (pinfunction "74_2") (pintype "passive"))
      (node (ref "R19") (pin "2") (pinfunction "74_2") (pintype "passive"))
      (node (ref "W1") (pin "31") (pinfunction "XO_31") (pintype "passive"))
      (node (ref "Y1") (pin "3") (pinfunction "2_3") (pintype "passive"))
    )
    (net (code "69") (name "Net-(C16-74)") (class "Default")
      (node (ref "C16") (pin "2") (pinfunction "74_2") (pintype "passive"))
      (node (ref "W1") (pin "20") (pinfunction "TOCAP_20") (pintype "passive"))
    )
    (net (code "70") (name "Net-(C17-74)") (class "Default")
      (node (ref "C17") (pin "2") (pinfunction "74_2") (pintype "passive"))
      (node (ref "W1") (pin "22") (pinfunction "1V20_22") (pintype "passive"))
    )
    (net (code "71") (name "Net-(C18-74)") (class "Default")
      (node (ref "C18") (pin "2") (pinfunction "74_2") (pintype "passive"))
      (node (ref "ETH1") (pin "5") (pinfunction "P5_5") (pintype "passive"))
      (node (ref "R21") (pin "1") (pinfunction "73_1") (pintype "passive"))
      (node (ref "R22") (pin "1") (pinfunction "73_1") (pintype "passive"))
    )
    (net (code "72") (name "Net-(C20-74)") (class "Default")
      (node (ref "C20") (pin "2") (pinfunction "74_2") (pintype "passive"))
      (node (ref "REG1") (pin "4") (pinfunction "ADJ_4") (pintype "passive"))
    )
    (net (code "73") (name "Net-(C21-74)") (class "Default")
      (node (ref "C21") (pin "2") (pinfunction "74_2") (pintype "passive"))
      (node (ref "R33") (pin "1") (pinfunction "73_1") (pintype "passive"))
      (node (ref "RST") (pin "1") (pinfunction "1_1") (pintype "passive"))
    )
    (net (code "74") (name "Net-(C28-74)") (class "Default")
      (node (ref "C28") (pin "2") (pinfunction "74_2") (pintype "passive"))
      (node (ref "U1") (pin "12") (pinfunction "PH0_12") (pintype "bidirectional"))
      (node (ref "Y2") (pin "1") (pinfunction "1_1") (pintype "passive"))
    )
    (net (code "75") (name "Net-(C29-74)") (class "Default")
      (node (ref "C29") (pin "2") (pinfunction "74_2") (pintype "passive"))
      (node (ref "U1") (pin "13") (pinfunction "PH1_13") (pintype "bidirectional"))
      (node (ref "Y2") (pin "3") (pinfunction "2_3") (pintype "passive"))
    )
    (net (code "76") (name "Net-(C32-82)") (class "Default")
      (node (ref "C32") (pin "2") (pinfunction "82_2") (pintype "passive"))
      (node (ref "U1") (pin "73") (pinfunction "VCAP_2_73") (pintype "passive"))
    )
    (net (code "77") (name "Net-(C33-82)") (class "Default")
      (node (ref "C33") (pin "2") (pinfunction "82_2") (pintype "passive"))
      (node (ref "U1") (pin "49") (pinfunction "VCAP_1_49") (pintype "passive"))
    )
    (net (code "78") (name "Net-(ETH1-GC)") (class "Default")
      (node (ref "ETH1") (pin "10") (pinfunction "GC_10") (pintype "passive"))
      (node (ref "R15") (pin "2") (pinfunction "74_2") (pintype "passive"))
    )
    (net (code "79") (name "Net-(ETH1-TD+)") (class "Default")
      (node (ref "ETH1") (pin "1") (pinfunction "TD+_1") (pintype "passive"))
      (node (ref "J1") (pin "3") (pinfunction "I/O2_3") (pintype "passive"))
      (node (ref "R2") (pin "1") (pinfunction "73_1") (pintype "passive"))
    )
    (net (code "80") (name "Net-(ETH1-TD-)") (class "Default")
      (node (ref "ETH1") (pin "2") (pinfunction "TD-_2") (pintype "passive"))
      (node (ref "J1") (pin "1") (pinfunction "I/O1_1") (pintype "passive"))
      (node (ref "R3") (pin "1") (pinfunction "73_1") (pintype "passive"))
    )
    (net (code "81") (name "Net-(ETH1-YC)") (class "Default")
      (node (ref "ETH1") (pin "11") (pinfunction "YC_11") (pintype "passive"))
      (node (ref "R16") (pin "2") (pinfunction "74_2") (pintype "passive"))
    )
    (net (code "82") (name "Net-(J1-I{slash}O3)") (class "Default")
      (node (ref "J1") (pin "4") (pinfunction "I/O3_4") (pintype "passive"))
      (node (ref "R17") (pin "1") (pinfunction "73_1") (pintype "passive"))
    )
    (net (code "83") (name "Net-(J1-I{slash}O4)") (class "Default")
      (node (ref "J1") (pin "6") (pinfunction "I/O4_6") (pintype "passive"))
      (node (ref "R14") (pin "1") (pinfunction "73_1") (pintype "passive"))
    )
    (net (code "84") (name "Net-(J2-I{slash}O3)") (class "Default")
      (node (ref "J2") (pin "4") (pinfunction "I/O3_4") (pintype "passive"))
      (node (ref "R20") (pin "1") (pinfunction "73_1") (pintype "passive"))
      (node (ref "R21") (pin "2") (pinfunction "74_2") (pintype "passive"))
    )
    (net (code "85") (name "Net-(J2-I{slash}O4)") (class "Default")
      (node (ref "J2") (pin "6") (pinfunction "I/O4_6") (pintype "passive"))
      (node (ref "R18") (pin "1") (pinfunction "73_1") (pintype "passive"))
      (node (ref "R22") (pin "2") (pinfunction "74_2") (pintype "passive"))
    )
    (net (code "86") (name "Net-(J3-SBU1)") (class "Default")
      (node (ref "J3") (pin "A8") (pinfunction "SBU1_A8") (pintype "bidirectional"))
      (node (ref "R26") (pin "2") (pinfunction "74_2") (pintype "passive"))
    )
    (net (code "87") (name "Net-(J3-SBU2)") (class "Default")
      (node (ref "J3") (pin "B8") (pinfunction "SBU2_B8") (pintype "bidirectional"))
      (node (ref "R25") (pin "1") (pinfunction "73_1") (pintype "passive"))
    )
    (net (code "88") (name "Net-(R4-73)") (class "Default")
      (node (ref "R4") (pin "1") (pinfunction "73_1") (pintype "passive"))
      (node (ref "W1") (pin "45") (pinfunction "PMODE0_45") (pintype "passive"))
    )
    (net (code "89") (name "Net-(R5-73)") (class "Default")
      (node (ref "R5") (pin "1") (pinfunction "73_1") (pintype "passive"))
      (node (ref "W1") (pin "44") (pinfunction "PMODE1_44") (pintype "passive"))
    )
    (net (code "90") (name "Net-(R6-73)") (class "Default")
      (node (ref "R6") (pin "1") (pinfunction "73_1") (pintype "passive"))
      (node (ref "W1") (pin "43") (pinfunction "PMODE2_43") (pintype "passive"))
    )
    (net (code "91") (name "Net-(R7-73)") (class "Default")
      (node (ref "R7") (pin "1") (pinfunction "73_1") (pintype "passive"))
      (node (ref "W1") (pin "42") (pinfunction "RSVD_42") (pintype "passive"))
    )
    (net (code "92") (name "Net-(R8-73)") (class "Default")
      (node (ref "R8") (pin "1") (pinfunction "73_1") (pintype "passive"))
      (node (ref "W1") (pin "41") (pinfunction "RSVD_41") (pintype "passive"))
    )
    (net (code "93") (name "Net-(R9-73)") (class "Default")
      (node (ref "R9") (pin "1") (pinfunction "73_1") (pintype "passive"))
      (node (ref "W1") (pin "40") (pinfunction "RSVD_40") (pintype "passive"))
    )
    (net (code "94") (name "Net-(R10-73)") (class "Default")
      (node (ref "R10") (pin "1") (pinfunction "73_1") (pintype "passive"))
      (node (ref "W1") (pin "39") (pinfunction "RSVD_39") (pintype "passive"))
    )
    (net (code "95") (name "Net-(R11-73)") (class "Default")
      (node (ref "R11") (pin "1") (pinfunction "73_1") (pintype "passive"))
      (node (ref "W1") (pin "38") (pinfunction "RSVD_38") (pintype "passive"))
    )
    (net (code "96") (name "Net-(R12-73)") (class "Default")
      (node (ref "R12") (pin "1") (pinfunction "73_1") (pintype "passive"))
      (node (ref "W1") (pin "37") (pinfunction "RSTn_37") (pintype "passive"))
    )
    (net (code "97") (name "Net-(R14-74)") (class "Default")
      (node (ref "R14") (pin "2") (pinfunction "74_2") (pintype "passive"))
      (node (ref "W1") (pin "1") (pinfunction "TXN_1") (pintype "passive"))
    )
    (net (code "98") (name "Net-(R17-74)") (class "Default")
      (node (ref "R17") (pin "2") (pinfunction "74_2") (pintype "passive"))
      (node (ref "W1") (pin "2") (pinfunction "TXP_2") (pintype "passive"))
    )
    (net (code "99") (name "Net-(R18-74)") (class "Default")
      (node (ref "R18") (pin "2") (pinfunction "74_2") (pintype "passive"))
      (node (ref "W1") (pin "5") (pinfunction "RXN_5") (pintype "passive"))
    )
    (net (code "100") (name "Net-(R20-74)") (class "Default")
      (node (ref "R20") (pin "2") (pinfunction "74_2") (pintype "passive"))
      (node (ref "W1") (pin "6") (pinfunction "RXP_6") (pintype "passive"))
    )
    (net (code "101") (name "Net-(R23-74)") (class "Default")
      (node (ref "R23") (pin "2") (pinfunction "74_2") (pintype "passive"))
      (node (ref "W1") (pin "10") (pinfunction "EXPRES1_10") (pintype "passive"))
    )
    (net (code "102") (name "Net-(R24-74)") (class "Default")
      (node (ref "R24") (pin "2") (pinfunction "74_2") (pintype "passive"))
      (node (ref "W1") (pin "23") (pinfunction "RSVD_23") (pintype "passive"))
    )
    (net (code "103") (name "Net-(R27-74)") (class "Default")
      (node (ref "R27") (pin "2") (pinfunction "74_2") (pintype "passive"))
      (node (ref "UTTL1") (pin "9") (pinfunction "~{RST}_9") (pintype "bidirectional"))
    )
    (net (code "104") (name "Net-(R28-73)") (class "Default")
      (node (ref "ON") (pin "C") (pinfunction "C_C") (pintype "passive"))
      (node (ref "R28") (pin "1") (pinfunction "73_1") (pintype "passive"))
    )
    (net (code "105") (name "Net-(R29-73)") (class "Default")
      (node (ref "R29") (pin "1") (pinfunction "73_1") (pintype "passive"))
      (node (ref "RXD") (pin "C") (pinfunction "C_C") (pintype "passive"))
    )
    (net (code "106") (name "Net-(R30-73)") (class "Default")
      (node (ref "R30") (pin "1") (pinfunction "73_1") (pintype "passive"))
      (node (ref "TXD") (pin "C") (pinfunction "C_C") (pintype "passive"))
    )
    (net (code "107") (name "Net-(R31-73)") (class "Default")
      (node (ref "R31") (pin "1") (pinfunction "73_1") (pintype "passive"))
      (node (ref "TX") (pin "C") (pinfunction "C_C") (pintype "passive"))
    )
    (net (code "108") (name "Net-(R32-73)") (class "Default")
      (node (ref "R32") (pin "1") (pinfunction "73_1") (pintype "passive"))
      (node (ref "RX") (pin "C") (pinfunction "C_C") (pintype "passive"))
    )
    (net (code "109") (name "Net-(R34-74)") (class "Default")
      (node (ref "BOOT") (pin "1") (pinfunction "1_1") (pintype "passive"))
      (node (ref "R34") (pin "2") (pinfunction "74_2") (pintype "passive"))
    )
    (net (code "110") (name "Net-(R35-73)") (class "Default")
      (node (ref "LED") (pin "C") (pinfunction "C_C") (pintype "passive"))
      (node (ref "R35") (pin "1") (pinfunction "73_1") (pintype "passive"))
    )
    (net (code "111") (name "unconnected-(J3-CC1-PadA5)") (class "Default")
      (node (ref "J3") (pin "A5") (pinfunction "CC1_A5") (pintype "bidirectional+no_connect"))
    )
    (net (code "112") (name "unconnected-(J3-CC2-PadB5)") (class "Default")
      (node (ref "J3") (pin "B5") (pinfunction "CC2_B5") (pintype "bidirectional+no_connect"))
    )
    (net (code "113") (name "unconnected-(J3-SHELL_GND-PadS1)") (class "Default")
      (node (ref "J3") (pin "S1") (pinfunction "SHELL_GND_S1") (pintype "power_in"))
    )
    (net (code "114") (name "unconnected-(J3-SHELL_GND-PadS2)") (class "Default")
      (node (ref "J3") (pin "S2") (pinfunction "SHELL_GND_S2") (pintype "power_in"))
    )
    (net (code "115") (name "unconnected-(J3-SHELL_GND-PadS3)") (class "Default")
      (node (ref "J3") (pin "S3") (pinfunction "SHELL_GND_S3") (pintype "power_in"))
    )
    (net (code "116") (name "unconnected-(J3-SHELL_GND-PadS4)") (class "Default")
      (node (ref "J3") (pin "S4") (pinfunction "SHELL_GND_S4") (pintype "power_in"))
    )
    (net (code "117") (name "unconnected-(ST-Link-Pad3)") (class "Default")
      (node (ref "ST-Link") (pin "3") (pintype "passive+no_connect"))
    )
    (net (code "118") (name "unconnected-(U1-PA0-Pad23)") (class "Default")
      (node (ref "U1") (pin "23") (pinfunction "PA0_23") (pintype "bidirectional+no_connect"))
    )
    (net (code "119") (name "unconnected-(U1-PA1-Pad24)") (class "Default")
      (node (ref "U1") (pin "24") (pinfunction "PA1_24") (pintype "bidirectional+no_connect"))
    )
    (net (code "120") (name "unconnected-(U1-PA13-Pad72)") (class "Default")
      (node (ref "U1") (pin "72") (pinfunction "PA13_72") (pintype "bidirectional+no_connect"))
    )
    (net (code "121") (name "unconnected-(U1-PA14-Pad76)") (class "Default")
      (node (ref "U1") (pin "76") (pinfunction "PA14_76") (pintype "bidirectional+no_connect"))
    )
    (net (code "122") (name "unconnected-(U1-PA15-Pad77)") (class "Default")
      (node (ref "U1") (pin "77") (pinfunction "PA15_77") (pintype "bidirectional+no_connect"))
    )
    (net (code "123") (name "unconnected-(U1-PB3-Pad89)") (class "Default")
      (node (ref "U1") (pin "89") (pinfunction "PB3_89") (pintype "bidirectional+no_connect"))
    )
    (net (code "124") (name "unconnected-(U1-PB4-Pad90)") (class "Default")
      (node (ref "U1") (pin "90") (pinfunction "PB4_90") (pintype "bidirectional+no_connect"))
    )
    (net (code "125") (name "unconnected-(U1-PB8-Pad95)") (class "Default")
      (node (ref "U1") (pin "95") (pinfunction "PB8_95") (pintype "bidirectional+no_connect"))
    )
    (net (code "126") (name "unconnected-(U1-PB9-Pad96)") (class "Default")
      (node (ref "U1") (pin "96") (pinfunction "PB9_96") (pintype "bidirectional+no_connect"))
    )
    (net (code "127") (name "unconnected-(U1-PB12-Pad51)") (class "Default")
      (node (ref "U1") (pin "51") (pinfunction "PB12_51") (pintype "bidirectional+no_connect"))
    )
    (net (code "128") (name "unconnected-(U1-PB13-Pad52)") (class "Default")
      (node (ref "U1") (pin "52") (pinfunction "PB13_52") (pintype "bidirectional+no_connect"))
    )
    (net (code "129") (name "unconnected-(U1-PC8-Pad65)") (class "Default")
      (node (ref "U1") (pin "65") (pinfunction "PC8_65") (pintype "bidirectional+no_connect"))
    )
    (net (code "130") (name "unconnected-(U1-PC14-Pad8)") (class "Default")
      (node (ref "U1") (pin "8") (pinfunction "PC14_8") (pintype "bidirectional+no_connect"))
    )
    (net (code "131") (name "unconnected-(U1-PC15-Pad9)") (class "Default")
      (node (ref "U1") (pin "9") (pinfunction "PC15_9") (pintype "bidirectional+no_connect"))
    )
    (net (code "132") (name "unconnected-(U1-PD0-Pad81)") (class "Default")
      (node (ref "U1") (pin "81") (pinfunction "PD0_81") (pintype "bidirectional+no_connect"))
    )
    (net (code "133") (name "unconnected-(U1-PD1-Pad82)") (class "Default")
      (node (ref "U1") (pin "82") (pinfunction "PD1_82") (pintype "bidirectional+no_connect"))
    )
    (net (code "134") (name "unconnected-(U1-PD3-Pad84)") (class "Default")
      (node (ref "U1") (pin "84") (pinfunction "PD3_84") (pintype "bidirectional+no_connect"))
    )
    (net (code "135") (name "unconnected-(U1-PD4-Pad85)") (class "Default")
      (node (ref "U1") (pin "85") (pinfunction "PD4_85") (pintype "bidirectional+no_connect"))
    )
    (net (code "136") (name "unconnected-(U1-PD5-Pad86)") (class "Default")
      (node (ref "U1") (pin "86") (pinfunction "PD5_86") (pintype "bidirectional+no_connect"))
    )
    (net (code "137") (name "unconnected-(U1-PD6-Pad87)") (class "Default")
      (node (ref "U1") (pin "87") (pinfunction "PD6_87") (pintype "bidirectional+no_connect"))
    )
    (net (code "138") (name "unconnected-(U1-PD7-Pad88)") (class "Default")
      (node (ref "U1") (pin "88") (pinfunction "PD7_88") (pintype "bidirectional+no_connect"))
    )
    (net (code "139") (name "unconnected-(U1-PD10-Pad57)") (class "Default")
      (node (ref "U1") (pin "57") (pinfunction "PD10_57") (pintype "bidirectional+no_connect"))
    )
    (net (code "140") (name "unconnected-(U1-PD11-Pad58)") (class "Default")
      (node (ref "U1") (pin "58") (pinfunction "PD11_58") (pintype "bidirectional+no_connect"))
    )
    (net (code "141") (name "unconnected-(U1-PD12-Pad59)") (class "Default")
      (node (ref "U1") (pin "59") (pinfunction "PD12_59") (pintype "bidirectional+no_connect"))
    )
    (net (code "142") (name "unconnected-(U1-PD13-Pad60)") (class "Default")
      (node (ref "U1") (pin "60") (pinfunction "PD13_60") (pintype "bidirectional+no_connect"))
    )
    (net (code "143") (name "unconnected-(U1-PD14-Pad61)") (class "Default")
      (node (ref "U1") (pin "61") (pinfunction "PD14_61") (pintype "bidirectional+no_connect"))
    )
    (net (code "144") (name "unconnected-(U1-PD15-Pad62)") (class "Default")
      (node (ref "U1") (pin "62") (pinfunction "PD15_62") (pintype "bidirectional+no_connect"))
    )
    (net (code "145") (name "unconnected-(U1-PE0-Pad97)") (class "Default")
      (node (ref "U1") (pin "97") (pinfunction "PE0_97") (pintype "bidirectional+no_connect"))
    )
    (net (code "146") (name "unconnected-(U1-PE1-Pad98)") (class "Default")
      (node (ref "U1") (pin "98") (pinfunction "PE1_98") (pintype "bidirectional+no_connect"))
    )
    (net (code "147") (name "unconnected-(U1-PE2-Pad1)") (class "Default")
      (node (ref "U1") (pin "1") (pinfunction "PE2_1") (pintype "bidirectional+no_connect"))
    )
    (net (code "148") (name "unconnected-(U1-PE3-Pad2)") (class "Default")
      (node (ref "U1") (pin "2") (pinfunction "PE3_2") (pintype "bidirectional+no_connect"))
    )
    (net (code "149") (name "unconnected-(U1-PE4-Pad3)") (class "Default")
      (node (ref "U1") (pin "3") (pinfunction "PE4_3") (pintype "bidirectional+no_connect"))
    )
    (net (code "150") (name "unconnected-(U1-PE5-Pad4)") (class "Default")
      (node (ref "U1") (pin "4") (pinfunction "PE5_4") (pintype "bidirectional+no_connect"))
    )
    (net (code "151") (name "unconnected-(U1-PE6-Pad5)") (class "Default")
      (node (ref "U1") (pin "5") (pinfunction "PE6_5") (pintype "bidirectional+no_connect"))
    )
    (net (code "152") (name "unconnected-(U1-VBAT-Pad6)") (class "Default")
      (node (ref "U1") (pin "6") (pinfunction "VBAT_6") (pintype "power_in+no_connect"))
    )
    (net (code "153") (name "unconnected-(UTTL1-CTS-Pad23)") (class "Default")
      (node (ref "UTTL1") (pin "23") (pinfunction "CTS_23") (pintype "input+no_connect"))
    )
    (net (code "154") (name "unconnected-(UTTL1-DCD-Pad1)") (class "Default")
      (node (ref "UTTL1") (pin "1") (pinfunction "DCD_1") (pintype "input+no_connect"))
    )
    (net (code "155") (name "unconnected-(UTTL1-DSR-Pad27)") (class "Default")
      (node (ref "UTTL1") (pin "27") (pinfunction "DSR_27") (pintype "input+no_connect"))
    )
    (net (code "156") (name "unconnected-(UTTL1-DTR-Pad28)") (class "Default")
      (node (ref "UTTL1") (pin "28") (pinfunction "DTR_28") (pintype "output+no_connect"))
    )
    (net (code "157") (name "unconnected-(UTTL1-NC-Pad10)") (class "Default")
      (node (ref "UTTL1") (pin "10") (pinfunction "NC_10") (pintype "passive+no_connect"))
    )
    (net (code "158") (name "unconnected-(UTTL1-NC-Pad13)") (class "Default")
      (node (ref "UTTL1") (pin "13") (pinfunction "NC_13") (pintype "passive+no_connect"))
    )
    (net (code "159") (name "unconnected-(UTTL1-NC-Pad14)") (class "Default")
      (node (ref "UTTL1") (pin "14") (pinfunction "NC_14") (pintype "passive+no_connect"))
    )
    (net (code "160") (name "unconnected-(UTTL1-NC-Pad15)") (class "Default")
      (node (ref "UTTL1") (pin "15") (pinfunction "NC_15") (pintype "passive+no_connect"))
    )
    (net (code "161") (name "unconnected-(UTTL1-NC-Pad16)") (class "Default")
      (node (ref "UTTL1") (pin "16") (pinfunction "NC_16") (pintype "passive+no_connect"))
    )
    (net (code "162") (name "unconnected-(UTTL1-NC-Pad17)") (class "Default")
      (node (ref "UTTL1") (pin "17") (pinfunction "NC_17") (pintype "passive+no_connect"))
    )
    (net (code "163") (name "unconnected-(UTTL1-NC-Pad18)") (class "Default")
      (node (ref "UTTL1") (pin "18") (pinfunction "NC_18") (pintype "passive+no_connect"))
    )
    (net (code "164") (name "unconnected-(UTTL1-NC-Pad19)") (class "Default")
      (node (ref "UTTL1") (pin "19") (pinfunction "NC_19") (pintype "passive+no_connect"))
    )
    (net (code "165") (name "unconnected-(UTTL1-NC-Pad20)") (class "Default")
      (node (ref "UTTL1") (pin "20") (pinfunction "NC_20") (pintype "passive+no_connect"))
    )
    (net (code "166") (name "unconnected-(UTTL1-NC-Pad21)") (class "Default")
      (node (ref "UTTL1") (pin "21") (pinfunction "NC_21") (pintype "passive+no_connect"))
    )
    (net (code "167") (name "unconnected-(UTTL1-NC-Pad22)") (class "Default")
      (node (ref "UTTL1") (pin "22") (pinfunction "NC_22") (pintype "passive+no_connect"))
    )
    (net (code "168") (name "unconnected-(UTTL1-RI-Pad2)") (class "Default")
      (node (ref "UTTL1") (pin "2") (pinfunction "RI_2") (pintype "input+no_connect"))
    )
    (net (code "169") (name "unconnected-(UTTL1-RTS-Pad24)") (class "Default")
      (node (ref "UTTL1") (pin "24") (pinfunction "RTS_24") (pintype "output+no_connect"))
    )
    (net (code "170") (name "unconnected-(UTTL1-SUSPEND-Pad12)") (class "Default")
      (node (ref "UTTL1") (pin "12") (pinfunction "SUSPEND_12") (pintype "output+no_connect"))
    )
    (net (code "171") (name "unconnected-(UTTL1-VDD-Pad6)") (class "Default")
      (node (ref "UTTL1") (pin "6") (pinfunction "VDD_6") (pintype "power_in+no_connect"))
    )
    (net (code "172") (name "unconnected-(UTTL1-~{SUSPEND}-Pad11)") (class "Default")
      (node (ref "UTTL1") (pin "11") (pinfunction "~{SUSPEND}_11") (pintype "output+no_connect"))
    )
    (net (code "173") (name "unconnected-(W1-DNC-Pad7)") (class "Default")
      (node (ref "W1") (pin "7") (pinfunction "DNC_7") (pintype "passive+no_connect"))
    )
    (net (code "174") (name "unconnected-(W1-DUPLED-Pad26)") (class "Default")
      (node (ref "W1") (pin "26") (pinfunction "DUPLED_26") (pintype "passive+no_connect"))
    )
    (net (code "175") (name "unconnected-(W1-NC-Pad12)") (class "Default")
      (node (ref "W1") (pin "12") (pinfunction "NC_12") (pintype "passive+no_connect"))
    )
    (net (code "176") (name "unconnected-(W1-NC-Pad13)") (class "Default")
      (node (ref "W1") (pin "13") (pinfunction "NC_13") (pintype "passive+no_connect"))
    )
    (net (code "177") (name "unconnected-(W1-NC-Pad46)") (class "Default")
      (node (ref "W1") (pin "46") (pinfunction "NC_46") (pintype "passive+no_connect"))
    )
    (net (code "178") (name "unconnected-(W1-NC-Pad47)") (class "Default")
      (node (ref "W1") (pin "47") (pinfunction "NC_47") (pintype "passive+no_connect"))
    )
    (net (code "179") (name "unconnected-(W1-SPDLED-Pad24)") (class "Default")
      (node (ref "W1") (pin "24") (pinfunction "SPDLED_24") (pintype "passive+no_connect"))
    )
    (net (code "180") (name "unconnected-(W1-VBG-Pad18)") (class "Default")
      (node (ref "W1") (pin "18") (pinfunction "VBG_18") (pintype "passive+no_connect"))
    )
  )
)
